# Coordination.net
KiCad netlist of a schematic drawn in Altium Designer
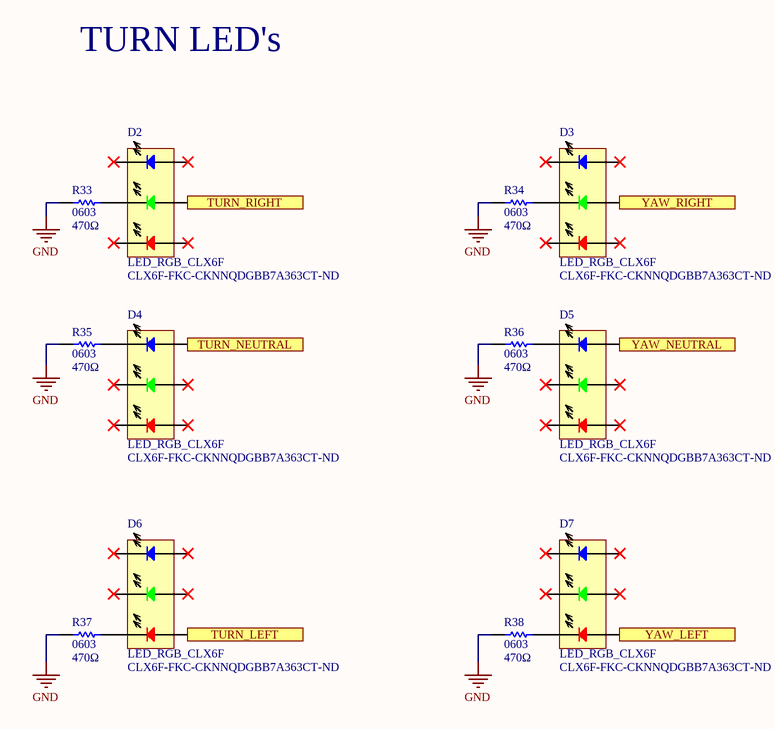
[diagram p0: Coordination.SchDoc]

(export (version "E")
  (design (tool "Eeschema 10.0.6"))
  (components
    (comp (ref "D2")
      (value "LED_RGB_CLX6F")
      (footprint "SKALE_LIB:SOJ100P350X290-6N")
      (description "Visible LED")
      (fields
        (field (name "MP") "CLX6F-FKC-CKNNQDGBB7A363")
        (field (name "DIGI-KEY_PART_NUMBER") "CLX6F-FKC-CKNNQDGBB7A363CT-ND")
        (field (name "SUPPLIER PART NUMBER 1") "CLX6F-FKC-CKNNQDGBB7A363CT-ND")
      )
      (libsource (lib "SKALE_LIB") (part "LED_RGB_CLX6F"))
    )
    (comp (ref "D3")
      (value "LED_RGB_CLX6F")
      (footprint "SKALE_LIB:SOJ100P350X290-6N")
      (description "Visible LED")
      (fields
        (field (name "MP") "CLX6F-FKC-CKNNQDGBB7A363")
        (field (name "DIGI-KEY_PART_NUMBER") "CLX6F-FKC-CKNNQDGBB7A363CT-ND")
        (field (name "SUPPLIER PART NUMBER 1") "CLX6F-FKC-CKNNQDGBB7A363CT-ND")
      )
      (libsource (lib "SKALE_LIB") (part "LED_RGB_CLX6F"))
    )
    (comp (ref "D4")
      (value "LED_RGB_CLX6F")
      (footprint "SKALE_LIB:SOJ100P350X290-6N")
      (description "Visible LED")
      (fields
        (field (name "MP") "CLX6F-FKC-CKNNQDGBB7A363")
        (field (name "DIGI-KEY_PART_NUMBER") "CLX6F-FKC-CKNNQDGBB7A363CT-ND")
        (field (name "SUPPLIER PART NUMBER 1") "CLX6F-FKC-CKNNQDGBB7A363CT-ND")
      )
      (libsource (lib "SKALE_LIB") (part "LED_RGB_CLX6F"))
    )
    (comp (ref "D5")
      (value "LED_RGB_CLX6F")
      (footprint "SKALE_LIB:SOJ100P350X290-6N")
      (description "Visible LED")
      (fields
        (field (name "MP") "CLX6F-FKC-CKNNQDGBB7A363")
        (field (name "DIGI-KEY_PART_NUMBER") "CLX6F-FKC-CKNNQDGBB7A363CT-ND")
        (field (name "SUPPLIER PART NUMBER 1") "CLX6F-FKC-CKNNQDGBB7A363CT-ND")
      )
      (libsource (lib "SKALE_LIB") (part "LED_RGB_CLX6F"))
    )
    (comp (ref "D6")
      (value "LED_RGB_CLX6F")
      (footprint "SKALE_LIB:SOJ100P350X290-6N")
      (description "Visible LED")
      (fields
        (field (name "MP") "CLX6F-FKC-CKNNQDGBB7A363")
        (field (name "DIGI-KEY_PART_NUMBER") "CLX6F-FKC-CKNNQDGBB7A363CT-ND")
        (field (name "SUPPLIER PART NUMBER 1") "CLX6F-FKC-CKNNQDGBB7A363CT-ND")
      )
      (libsource (lib "SKALE_LIB") (part "LED_RGB_CLX6F"))
    )
    (comp (ref "D7")
      (value "LED_RGB_CLX6F")
      (footprint "SKALE_LIB:SOJ100P350X290-6N")
      (description "Visible LED")
      (fields
        (field (name "MP") "CLX6F-FKC-CKNNQDGBB7A363")
        (field (name "DIGI-KEY_PART_NUMBER") "CLX6F-FKC-CKNNQDGBB7A363CT-ND")
        (field (name "SUPPLIER PART NUMBER 1") "CLX6F-FKC-CKNNQDGBB7A363CT-ND")
      )
      (libsource (lib "SKALE_LIB") (part "LED_RGB_CLX6F"))
    )
    (comp (ref "R33")
      (value "470Ω")
      (footprint "RES0603")
      (description "RES 470 OHM 1% 1/10W 0603")
      (fields (field (name "FOOTPRINT SIZE") "0603") (field (name "Comment") "470R 1%"))
      (libsource (lib "SKALE_LIB") (part "RES_470Ω_0603_1%"))
    )
    (comp (ref "R34")
      (value "470Ω")
      (footprint "RES0603")
      (description "RES 470 OHM 1% 1/10W 0603")
      (fields (field (name "FOOTPRINT SIZE") "0603") (field (name "Comment") "470R 1%"))
      (libsource (lib "SKALE_LIB") (part "RES_470Ω_0603_1%"))
    )
    (comp (ref "R35")
      (value "470Ω")
      (footprint "RES0603")
      (description "RES 470 OHM 1% 1/10W 0603")
      (fields (field (name "FOOTPRINT SIZE") "0603") (field (name "Comment") "470R 1%"))
      (libsource (lib "SKALE_LIB") (part "RES_470Ω_0603_1%"))
    )
    (comp (ref "R36")
      (value "470Ω")
      (footprint "RES0603")
      (description "RES 470 OHM 1% 1/10W 0603")
      (fields (field (name "FOOTPRINT SIZE") "0603") (field (name "Comment") "470R 1%"))
      (libsource (lib "SKALE_LIB") (part "RES_470Ω_0603_1%"))
    )
    (comp (ref "R37")
      (value "470Ω")
      (footprint "RES0603")
      (description "RES 470 OHM 1% 1/10W 0603")
      (fields (field (name "FOOTPRINT SIZE") "0603") (field (name "Comment") "470R 1%"))
      (libsource (lib "SKALE_LIB") (part "RES_470Ω_0603_1%"))
    )
    (comp (ref "R38")
      (value "470Ω")
      (footprint "RES0603")
      (description "RES 470 OHM 1% 1/10W 0603")
      (fields (field (name "FOOTPRINT SIZE") "0603") (field (name "Comment") "470R 1%"))
      (libsource (lib "SKALE_LIB") (part "RES_470Ω_0603_1%"))
    )
  )
  (nets
    (net (code "1") (name "/TURN_LEFT") (class "Default")
      (node (ref "D6") (pin "4") (pinfunction "Red_+_4") (pintype "passive"))
    )
    (net (code "2") (name "/TURN_NEUTRAL") (class "Default")
      (node (ref "D4") (pin "6") (pinfunction "Blue_+_6") (pintype "passive"))
    )
    (net (code "3") (name "/TURN_RIGHT") (class "Default")
      (node (ref "D2") (pin "5") (pinfunction "Green_+_5") (pintype "passive"))
    )
    (net (code "4") (name "/YAW_LEFT") (class "Default")
      (node (ref "D7") (pin "4") (pinfunction "Red_+_4") (pintype "passive"))
    )
    (net (code "5") (name "/YAW_NEUTRAL") (class "Default")
      (node (ref "D5") (pin "6") (pinfunction "Blue_+_6") (pintype "passive"))
    )
    (net (code "6") (name "/YAW_RIGHT") (class "Default")
      (node (ref "D3") (pin "5") (pinfunction "Green_+_5") (pintype "passive"))
    )
    (net (code "7") (name "GND") (class "Default")
      (node (ref "R33") (pin "1") (pinfunction "1_1") (pintype "passive"))
      (node (ref "R34") (pin "1") (pinfunction "1_1") (pintype "passive"))
      (node (ref "R35") (pin "1") (pinfunction "1_1") (pintype "passive"))
      (node (ref "R36") (pin "1") (pinfunction "1_1") (pintype "passive"))
      (node (ref "R37") (pin "1") (pinfunction "1_1") (pintype "passive"))
      (node (ref "R38") (pin "1") (pinfunction "1_1") (pintype "passive"))
    )
    (net (code "8") (name "Net-(D2-GREEN_-)") (class "Default")
      (node (ref "D2") (pin "2") (pinfunction "GREEN_-_2") (pintype "passive"))
      (node (ref "R33") (pin "2") (pinfunction "2_2") (pintype "passive"))
    )
    (net (code "9") (name "Net-(D3-GREEN_-)") (class "Default")
      (node (ref "D3") (pin "2") (pinfunction "GREEN_-_2") (pintype "passive"))
      (node (ref "R34") (pin "2") (pinfunction "2_2") (pintype "passive"))
    )
    (net (code "10") (name "Net-(D4-BLUE_-)") (class "Default")
      (node (ref "D4") (pin "1") (pinfunction "BLUE_-_1") (pintype "passive"))
      (node (ref "R35") (pin "2") (pinfunction "2_2") (pintype "passive"))
    )
    (net (code "11") (name "Net-(D5-BLUE_-)") (class "Default")
      (node (ref "D5") (pin "1") (pinfunction "BLUE_-_1") (pintype "passive"))
      (node (ref "R36") (pin "2") (pinfunction "2_2") (pintype "passive"))
    )
    (net (code "12") (name "Net-(D6-RED_-)") (class "Default")
      (node (ref "D6") (pin "3") (pinfunction "RED_-_3") (pintype "passive"))
      (node (ref "R37") (pin "2") (pinfunction "2_2") (pintype "passive"))
    )
    (net (code "13") (name "Net-(D7-RED_-)") (class "Default")
      (node (ref "D7") (pin "3") (pinfunction "RED_-_3") (pintype "passive"))
      (node (ref "R38") (pin "2") (pinfunction "2_2") (pintype "passive"))
    )
    (net (code "14") (name "unconnected-(D2-BLUE_--Pad1)") (class "Default")
      (node (ref "D2") (pin "1") (pinfunction "BLUE_-_1") (pintype "passive+no_connect"))
    )
    (net (code "15") (name "unconnected-(D2-Blue_+-Pad6)") (class "Default")
      (node (ref "D2") (pin "6") (pinfunction "Blue_+_6") (pintype "passive+no_connect"))
    )
    (net (code "16") (name "unconnected-(D2-RED_--Pad3)") (class "Default")
      (node (ref "D2") (pin "3") (pinfunction "RED_-_3") (pintype "passive+no_connect"))
    )
    (net (code "17") (name "unconnected-(D2-Red_+-Pad4)") (class "Default")
      (node (ref "D2") (pin "4") (pinfunction "Red_+_4") (pintype "passive+no_connect"))
    )
    (net (code "18") (name "unconnected-(D3-BLUE_--Pad1)") (class "Default")
      (node (ref "D3") (pin "1") (pinfunction "BLUE_-_1") (pintype "passive+no_connect"))
    )
    (net (code "19") (name "unconnected-(D3-Blue_+-Pad6)") (class "Default")
      (node (ref "D3") (pin "6") (pinfunction "Blue_+_6") (pintype "passive+no_connect"))
    )
    (net (code "20") (name "unconnected-(D3-RED_--Pad3)") (class "Default")
      (node (ref "D3") (pin "3") (pinfunction "RED_-_3") (pintype "passive+no_connect"))
    )
    (net (code "21") (name "unconnected-(D3-Red_+-Pad4)") (class "Default")
      (node (ref "D3") (pin "4") (pinfunction "Red_+_4") (pintype "passive+no_connect"))
    )
    (net (code "22") (name "unconnected-(D4-GREEN_--Pad2)") (class "Default")
      (node (ref "D4") (pin "2") (pinfunction "GREEN_-_2") (pintype "passive+no_connect"))
    )
    (net (code "23") (name "unconnected-(D4-Green_+-Pad5)") (class "Default")
      (node (ref "D4") (pin "5") (pinfunction "Green_+_5") (pintype "passive+no_connect"))
    )
    (net (code "24") (name "unconnected-(D4-RED_--Pad3)") (class "Default")
      (node (ref "D4") (pin "3") (pinfunction "RED_-_3") (pintype "passive+no_connect"))
    )
    (net (code "25") (name "unconnected-(D4-Red_+-Pad4)") (class "Default")
      (node (ref "D4") (pin "4") (pinfunction "Red_+_4") (pintype "passive+no_connect"))
    )
    (net (code "26") (name "unconnected-(D5-GREEN_--Pad2)") (class "Default")
      (node (ref "D5") (pin "2") (pinfunction "GREEN_-_2") (pintype "passive+no_connect"))
    )
    (net (code "27") (name "unconnected-(D5-Green_+-Pad5)") (class "Default")
      (node (ref "D5") (pin "5") (pinfunction "Green_+_5") (pintype "passive+no_connect"))
    )
    (net (code "28") (name "unconnected-(D5-RED_--Pad3)") (class "Default")
      (node (ref "D5") (pin "3") (pinfunction "RED_-_3") (pintype "passive+no_connect"))
    )
    (net (code "29") (name "unconnected-(D5-Red_+-Pad4)") (class "Default")
      (node (ref "D5") (pin "4") (pinfunction "Red_+_4") (pintype "passive+no_connect"))
    )
    (net (code "30") (name "unconnected-(D6-BLUE_--Pad1)") (class "Default")
      (node (ref "D6") (pin "1") (pinfunction "BLUE_-_1") (pintype "passive+no_connect"))
    )
    (net (code "31") (name "unconnected-(D6-Blue_+-Pad6)") (class "Default")
      (node (ref "D6") (pin "6") (pinfunction "Blue_+_6") (pintype "passive+no_connect"))
    )
    (net (code "32") (name "unconnected-(D6-GREEN_--Pad2)") (class "Default")
      (node (ref "D6") (pin "2") (pinfunction "GREEN_-_2") (pintype "passive+no_connect"))
    )
    (net (code "33") (name "unconnected-(D6-Green_+-Pad5)") (class "Default")
      (node (ref "D6") (pin "5") (pinfunction "Green_+_5") (pintype "passive+no_connect"))
    )
    (net (code "34") (name "unconnected-(D7-BLUE_--Pad1)") (class "Default")
      (node (ref "D7") (pin "1") (pinfunction "BLUE_-_1") (pintype "passive+no_connect"))
    )
    (net (code "35") (name "unconnected-(D7-Blue_+-Pad6)") (class "Default")
      (node (ref "D7") (pin "6") (pinfunction "Blue_+_6") (pintype "passive+no_connect"))
    )
    (net (code "36") (name "unconnected-(D7-GREEN_--Pad2)") (class "Default")
      (node (ref "D7") (pin "2") (pinfunction "GREEN_-_2") (pintype "passive+no_connect"))
    )
    (net (code "37") (name "unconnected-(D7-Green_+-Pad5)") (class "Default")
      (node (ref "D7") (pin "5") (pinfunction "Green_+_5") (pintype "passive+no_connect"))
    )
  )
)
